# Sheet1.net
KiCad netlist of a schematic drawn in Altium Designer
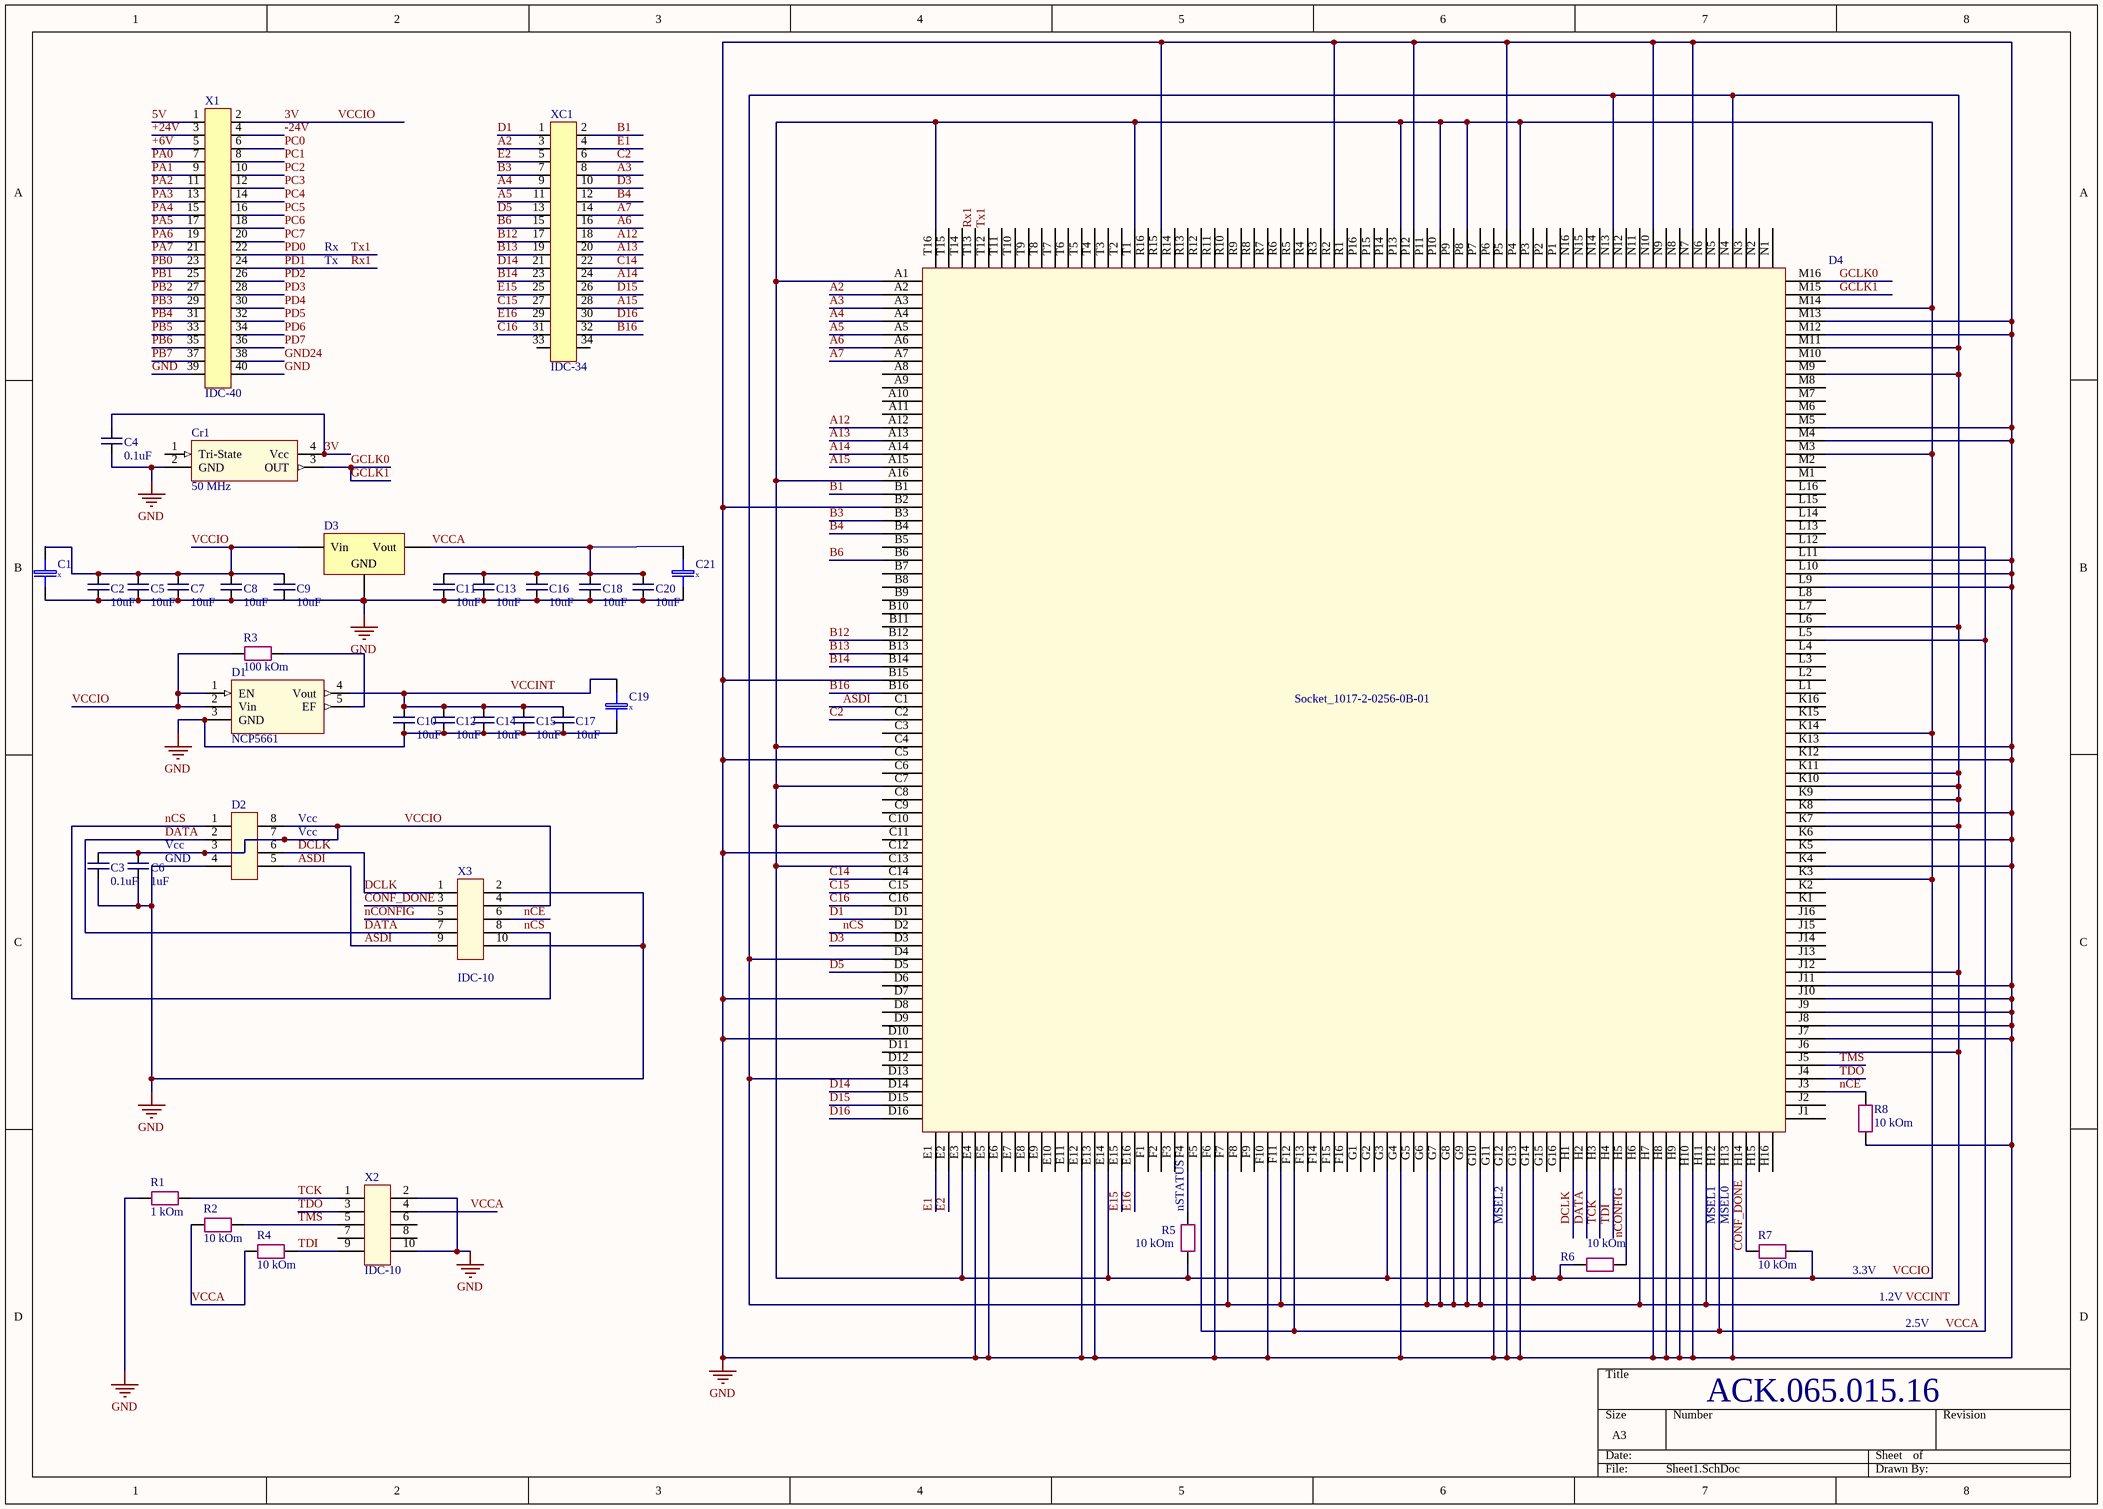
[diagram p0: Sheet1.SchDoc]

(export (version "E")
  (design (tool "Eeschema 10.0.6"))
  (components
    (comp (ref "C1")
      (value "x")
      (footprint "EL Case D (7343-31)")
      (description "EL Tantalum Case D (7343-31)")
      (libsource (lib "SMD-RCL") (part "EL Case D (7343-31)"))
    )
    (comp (ref "C2") (value "10uF") (footprint "RCU:C_0805") (libsource (lib "RCU") (part "capacitor 0805")))
    (comp (ref "C3") (value "0.1uF") (footprint "RCU:C_0805") (libsource (lib "RCU") (part "capacitor 0805")))
    (comp (ref "C4") (value "0.1uF") (footprint "RCU:C_0805") (libsource (lib "RCU") (part "capacitor 0805")))
    (comp (ref "C5") (value "10uF") (footprint "RCU:C_0805") (libsource (lib "RCU") (part "capacitor 0805")))
    (comp (ref "C6") (value "1uF") (footprint "RCU:C_0805") (libsource (lib "RCU") (part "capacitor 0805")))
    (comp (ref "C7") (value "10uF") (footprint "RCU:C_0805") (libsource (lib "RCU") (part "capacitor 0805")))
    (comp (ref "C8") (value "10uF") (footprint "RCU:C_0805") (libsource (lib "RCU") (part "capacitor 0805")))
    (comp (ref "C9") (value "10uF") (footprint "RCU:C_0805") (libsource (lib "RCU") (part "capacitor 0805")))
    (comp (ref "C10") (value "10uF") (footprint "RCU:C_0805") (libsource (lib "RCU") (part "capacitor 0805")))
    (comp (ref "C11") (value "10uF") (footprint "RCU:C_0805") (libsource (lib "RCU") (part "capacitor 0805")))
    (comp (ref "C12") (value "10uF") (footprint "RCU:C_0805") (libsource (lib "RCU") (part "capacitor 0805")))
    (comp (ref "C13") (value "10uF") (footprint "RCU:C_0805") (libsource (lib "RCU") (part "capacitor 0805")))
    (comp (ref "C14") (value "10uF") (footprint "RCU:C_0805") (libsource (lib "RCU") (part "capacitor 0805")))
    (comp (ref "C15") (value "10uF") (footprint "RCU:C_0805") (libsource (lib "RCU") (part "capacitor 0805")))
    (comp (ref "C16") (value "10uF") (footprint "RCU:C_0805") (libsource (lib "RCU") (part "capacitor 0805")))
    (comp (ref "C17") (value "10uF") (footprint "RCU:C_0805") (libsource (lib "RCU") (part "capacitor 0805")))
    (comp (ref "C18") (value "10uF") (footprint "RCU:C_0805") (libsource (lib "RCU") (part "capacitor 0805")))
    (comp (ref "C19")
      (value "x")
      (footprint "EL Case D (7343-31)")
      (description "EL Tantalum Case D (7343-31)")
      (libsource (lib "SMD-RCL") (part "EL Case D (7343-31)"))
    )
    (comp (ref "C20") (value "10uF") (footprint "RCU:C_0805") (libsource (lib "RCU") (part "capacitor 0805")))
    (comp (ref "C21")
      (value "x")
      (footprint "EL Case D (7343-31)")
      (description "EL Tantalum Case D (7343-31)")
      (libsource (lib "SMD-RCL") (part "EL Case D (7343-31)"))
    )
    (comp (ref "Cr1")
      (value "50 MHz")
      (footprint "quartz gen smd 5032")
      (libsource (lib "RCU") (part "quartz gen 5032"))
    )
    (comp (ref "D1") (value "NCP5661") (footprint "TO114P990-5_6M") (libsource (lib "RCU") (part "NCP5661")))
    (comp (ref "D2") (value "SOIC-8") (footprint "SOIC-8") (libsource (lib "RCU") (part "SOIC-8")))
    (comp (ref "D3")
      (value "LM1117-3.3")
      (footprint "TO252AA")
      (description "Voltage Regulator")
      (fields (field (name "PUBLISHER") "Altium Limited"))
      (libsource (lib "Miscellaneous Devices") (part "Volt Reg"))
    )
    (comp (ref "D4")
      (value "Socket_1017-2-0256-0B-01")
      (footprint "FBGA256")
      (libsource (lib "RCU") (part "Socket_1017-2-0256-0B-01"))
    )
    (comp (ref "R1") (value "1 kOm") (footprint "RCU:R_0805") (libsource (lib "RCU") (part "resistor 0805")))
    (comp (ref "R2") (value "10 kOm") (footprint "RCU:R_0805") (libsource (lib "RCU") (part "resistor 0805")))
    (comp (ref "R3")
      (value "100 kOm")
      (footprint "RCU:R_0805")
      (libsource (lib "RCU") (part "resistor 0805"))
    )
    (comp (ref "R4") (value "10 kOm") (footprint "RCU:R_0805") (libsource (lib "RCU") (part "resistor 0805")))
    (comp (ref "R5") (value "10 kOm") (footprint "RCU:R_0805") (libsource (lib "RCU") (part "resistor 0805")))
    (comp (ref "R6") (value "10 kOm") (footprint "RCU:R_0805") (libsource (lib "RCU") (part "resistor 0805")))
    (comp (ref "R7") (value "10 kOm") (footprint "RCU:R_0805") (libsource (lib "RCU") (part "resistor 0805")))
    (comp (ref "R8") (value "10 kOm") (footprint "RCU:R_0805") (libsource (lib "RCU") (part "resistor 0805")))
    (comp (ref "X1")
      (value "IDC-40")
      (footprint "IDC-40")
      (description "разъем 2529")
      (libsource (lib "RCU") (part "IDC-40"))
    )
    (comp (ref "X2")
      (value "IDC-10")
      (footprint "IDC-10")
      (description "разъем 4130")
      (libsource (lib "RCU") (part "IDC-10"))
    )
    (comp (ref "X3")
      (value "IDC-10")
      (footprint "IDC-10")
      (description "разъем 4130")
      (libsource (lib "RCU") (part "IDC-10"))
    )
    (comp (ref "XC1")
      (value "IDC-34")
      (footprint "IDC-34")
      (description "разъем 6556")
      (libsource (lib "RCU") (part "IDC-34"))
    )
  )
  (nets
    (net (code "1") (name "/+6V") (class "Default")
      (node (ref "X1") (pin "5") (pinfunction "5_5") (pintype "passive"))
    )
    (net (code "2") (name "/+24V") (class "Default")
      (node (ref "X1") (pin "3") (pinfunction "3_3") (pintype "passive"))
    )
    (net (code "3") (name "/-24V") (class "Default")
      (node (ref "X1") (pin "4") (pinfunction "4_4") (pintype "passive"))
    )
    (net (code "4") (name "/3V") (class "Default")
      (node (ref "C1") (pin "1") (pinfunction "+_1") (pintype "passive"))
      (node (ref "C2") (pin "2") (pinfunction "2_2") (pintype "passive"))
      (node (ref "C3") (pin "2") (pinfunction "2_2") (pintype "passive"))
      (node (ref "C4") (pin "2") (pinfunction "2_2") (pintype "passive"))
      (node (ref "C5") (pin "2") (pinfunction "2_2") (pintype "passive"))
      (node (ref "C6") (pin "2") (pinfunction "2_2") (pintype "passive"))
      (node (ref "C7") (pin "2") (pinfunction "2_2") (pintype "passive"))
      (node (ref "C8") (pin "2") (pinfunction "2_2") (pintype "passive"))
      (node (ref "C9") (pin "2") (pinfunction "2_2") (pintype "passive"))
      (node (ref "Cr1") (pin "4") (pinfunction "Vcc_4") (pintype "power_in"))
      (node (ref "D1") (pin "1") (pinfunction "EN_1") (pintype "input"))
      (node (ref "D1") (pin "2") (pinfunction "Vin_2") (pintype "power_in"))
      (node (ref "D2") (pin "3") (pinfunction "3_3") (pintype "passive"))
      (node (ref "D2") (pin "7") (pinfunction "7_7") (pintype "passive"))
      (node (ref "D2") (pin "8") (pinfunction "8_8") (pintype "passive"))
      (node (ref "D3") (pin "1") (pinfunction "Vin_1") (pintype "passive"))
      (node (ref "D4") (pin "A1") (pinfunction "A1_A1") (pintype "passive"))
      (node (ref "D4") (pin "A16") (pinfunction "A16_A16") (pintype "passive"))
      (node (ref "D4") (pin "C10") (pinfunction "C10_C10") (pintype "passive"))
      (node (ref "D4") (pin "C13") (pinfunction "C13_C13") (pintype "passive"))
      (node (ref "D4") (pin "C4") (pinfunction "C4_C4") (pintype "passive"))
      (node (ref "D4") (pin "C7") (pinfunction "C7_C7") (pintype "passive"))
      (node (ref "D4") (pin "E14") (pinfunction "E14_E14") (pintype "passive"))
      (node (ref "D4") (pin "E3") (pinfunction "E3_E3") (pintype "passive"))
      (node (ref "D4") (pin "G14") (pinfunction "G14_G14") (pintype "passive"))
      (node (ref "D4") (pin "G3") (pinfunction "G3_G3") (pintype "passive"))
      (node (ref "D4") (pin "K14") (pinfunction "K14_K14") (pintype "passive"))
      (node (ref "D4") (pin "K3") (pinfunction "K3_K3") (pintype "passive"))
      (node (ref "D4") (pin "M14") (pinfunction "M14_M14") (pintype "passive"))
      (node (ref "D4") (pin "M3") (pinfunction "M3_M3") (pintype "passive"))
      (node (ref "D4") (pin "P10") (pinfunction "P10_P10") (pintype "passive"))
      (node (ref "D4") (pin "P13") (pinfunction "P13_P13") (pintype "passive"))
      (node (ref "D4") (pin "P4") (pinfunction "P4_P4") (pintype "passive"))
      (node (ref "D4") (pin "P8") (pinfunction "P8_P8") (pintype "passive"))
      (node (ref "D4") (pin "T1") (pinfunction "T1_T1") (pintype "passive"))
      (node (ref "D4") (pin "T16") (pinfunction "T16_T16") (pintype "passive"))
      (node (ref "R3") (pin "1") (pinfunction "1_1") (pintype "passive"))
      (node (ref "R5") (pin "2") (pinfunction "2_2") (pintype "passive"))
      (node (ref "R6") (pin "1") (pinfunction "1_1") (pintype "passive"))
      (node (ref "R7") (pin "2") (pinfunction "2_2") (pintype "passive"))
      (node (ref "X1") (pin "2") (pinfunction "2_2") (pintype "passive"))
      (node (ref "X3") (pin "4") (pinfunction "4_4") (pintype "passive"))
    )
    (net (code "5") (name "/5V") (class "Default")
      (node (ref "X1") (pin "1") (pinfunction "0_1") (pintype "passive"))
    )
    (net (code "6") (name "/A2") (class "Default")
      (node (ref "D4") (pin "A2") (pinfunction "A2_A2") (pintype "passive"))
      (node (ref "XC1") (pin "3") (pinfunction "3_3") (pintype "passive"))
    )
    (net (code "7") (name "/A3") (class "Default")
      (node (ref "D4") (pin "A3") (pinfunction "A3_A3") (pintype "passive"))
      (node (ref "XC1") (pin "8") (pinfunction "8_8") (pintype "passive"))
    )
    (net (code "8") (name "/A4") (class "Default")
      (node (ref "D4") (pin "A4") (pinfunction "A4_A4") (pintype "passive"))
      (node (ref "XC1") (pin "9") (pinfunction "9_9") (pintype "passive"))
    )
    (net (code "9") (name "/A5") (class "Default")
      (node (ref "D4") (pin "A5") (pinfunction "A5_A5") (pintype "passive"))
      (node (ref "XC1") (pin "11") (pinfunction "11_11") (pintype "passive"))
    )
    (net (code "10") (name "/A6") (class "Default")
      (node (ref "D4") (pin "A6") (pinfunction "A6_A6") (pintype "passive"))
      (node (ref "XC1") (pin "16") (pinfunction "16_16") (pintype "passive"))
    )
    (net (code "11") (name "/A7") (class "Default")
      (node (ref "D4") (pin "A7") (pinfunction "A7_A7") (pintype "passive"))
      (node (ref "XC1") (pin "14") (pinfunction "14_14") (pintype "passive"))
    )
    (net (code "12") (name "/A12") (class "Default")
      (node (ref "D4") (pin "A12") (pinfunction "A12_A12") (pintype "passive"))
      (node (ref "XC1") (pin "18") (pinfunction "18_18") (pintype "passive"))
    )
    (net (code "13") (name "/A13") (class "Default")
      (node (ref "D4") (pin "A13") (pinfunction "A13_A13") (pintype "passive"))
      (node (ref "XC1") (pin "20") (pinfunction "20_20") (pintype "passive"))
    )
    (net (code "14") (name "/A14") (class "Default")
      (node (ref "D4") (pin "A14") (pinfunction "A14_A14") (pintype "passive"))
      (node (ref "XC1") (pin "24") (pinfunction "24_24") (pintype "passive"))
    )
    (net (code "15") (name "/A15") (class "Default")
      (node (ref "D4") (pin "A15") (pinfunction "A15_A15") (pintype "passive"))
      (node (ref "XC1") (pin "28") (pinfunction "28_28") (pintype "passive"))
    )
    (net (code "16") (name "/ASDI") (class "Default")
      (node (ref "D2") (pin "5") (pinfunction "5_5") (pintype "passive"))
      (node (ref "D4") (pin "C1") (pinfunction "C1_C1") (pintype "passive"))
      (node (ref "X3") (pin "9") (pinfunction "9_9") (pintype "passive"))
    )
    (net (code "17") (name "/B1") (class "Default")
      (node (ref "D4") (pin "B1") (pinfunction "B1_B1") (pintype "passive"))
      (node (ref "XC1") (pin "2") (pinfunction "2_2") (pintype "passive"))
    )
    (net (code "18") (name "/B3") (class "Default")
      (node (ref "D4") (pin "B3") (pinfunction "B3_B3") (pintype "passive"))
      (node (ref "XC1") (pin "7") (pinfunction "7_7") (pintype "passive"))
    )
    (net (code "19") (name "/B4") (class "Default")
      (node (ref "D4") (pin "B4") (pinfunction "B4_B4") (pintype "passive"))
      (node (ref "XC1") (pin "12") (pinfunction "12_12") (pintype "passive"))
    )
    (net (code "20") (name "/B6") (class "Default")
      (node (ref "D4") (pin "B6") (pinfunction "B6_B6") (pintype "passive"))
      (node (ref "XC1") (pin "15") (pinfunction "15_15") (pintype "passive"))
    )
    (net (code "21") (name "/B12") (class "Default")
      (node (ref "D4") (pin "B12") (pinfunction "B12_B12") (pintype "passive"))
      (node (ref "XC1") (pin "17") (pinfunction "17_17") (pintype "passive"))
    )
    (net (code "22") (name "/B13") (class "Default")
      (node (ref "D4") (pin "B13") (pinfunction "B13_B13") (pintype "passive"))
      (node (ref "XC1") (pin "19") (pinfunction "19_19") (pintype "passive"))
    )
    (net (code "23") (name "/B14") (class "Default")
      (node (ref "D4") (pin "B14") (pinfunction "B14_B14") (pintype "passive"))
      (node (ref "XC1") (pin "23") (pinfunction "23_23") (pintype "passive"))
    )
    (net (code "24") (name "/B16") (class "Default")
      (node (ref "D4") (pin "B16") (pinfunction "B16_B16") (pintype "passive"))
      (node (ref "XC1") (pin "32") (pinfunction "32_32") (pintype "passive"))
    )
    (net (code "25") (name "/C2") (class "Default")
      (node (ref "D4") (pin "C2") (pinfunction "C2_C2") (pintype "passive"))
      (node (ref "XC1") (pin "6") (pinfunction "6_6") (pintype "passive"))
    )
    (net (code "26") (name "/C14") (class "Default")
      (node (ref "D4") (pin "C14") (pinfunction "C14_C14") (pintype "passive"))
      (node (ref "XC1") (pin "22") (pinfunction "22_22") (pintype "passive"))
    )
    (net (code "27") (name "/C15") (class "Default")
      (node (ref "D4") (pin "C15") (pinfunction "C15_C15") (pintype "passive"))
      (node (ref "XC1") (pin "27") (pinfunction "27_27") (pintype "passive"))
    )
    (net (code "28") (name "/C16") (class "Default")
      (node (ref "D4") (pin "C16") (pinfunction "C16_C16") (pintype "passive"))
      (node (ref "XC1") (pin "31") (pinfunction "31_31") (pintype "passive"))
    )
    (net (code "29") (name "/CONF_DONE") (class "Default")
      (node (ref "D4") (pin "H14") (pinfunction "H14_H14") (pintype "passive"))
      (node (ref "R7") (pin "1") (pinfunction "1_1") (pintype "passive"))
      (node (ref "X3") (pin "3") (pinfunction "3_3") (pintype "passive"))
    )
    (net (code "30") (name "/D1") (class "Default")
      (node (ref "D4") (pin "D1") (pinfunction "D1_D1") (pintype "passive"))
      (node (ref "XC1") (pin "1") (pinfunction "0_1") (pintype "passive"))
    )
    (net (code "31") (name "/D3") (class "Default")
      (node (ref "D4") (pin "D3") (pinfunction "D3_D3") (pintype "passive"))
      (node (ref "XC1") (pin "10") (pinfunction "10_10") (pintype "passive"))
    )
    (net (code "32") (name "/D5") (class "Default")
      (node (ref "D4") (pin "D5") (pinfunction "D5_D5") (pintype "passive"))
      (node (ref "XC1") (pin "13") (pinfunction "13_13") (pintype "passive"))
    )
    (net (code "33") (name "/D14") (class "Default")
      (node (ref "D4") (pin "D14") (pinfunction "D14_D14") (pintype "passive"))
      (node (ref "XC1") (pin "21") (pinfunction "21_21") (pintype "passive"))
    )
    (net (code "34") (name "/D15") (class "Default")
      (node (ref "D4") (pin "D15") (pinfunction "D15_D15") (pintype "passive"))
      (node (ref "XC1") (pin "26") (pinfunction "26_26") (pintype "passive"))
    )
    (net (code "35") (name "/D16") (class "Default")
      (node (ref "D4") (pin "D16") (pinfunction "D16_D16") (pintype "passive"))
      (node (ref "XC1") (pin "30") (pinfunction "30_30") (pintype "passive"))
    )
    (net (code "36") (name "/DATA") (class "Default")
      (node (ref "D2") (pin "2") (pinfunction "2_2") (pintype "passive"))
      (node (ref "D4") (pin "H2") (pinfunction "H2_H2") (pintype "passive"))
      (node (ref "X3") (pin "7") (pinfunction "7_7") (pintype "passive"))
    )
    (net (code "37") (name "/DCLK") (class "Default")
      (node (ref "D2") (pin "6") (pinfunction "6_6") (pintype "passive"))
      (node (ref "D4") (pin "H1") (pinfunction "H1_H1") (pintype "passive"))
      (node (ref "X3") (pin "1") (pinfunction "1_1") (pintype "passive"))
    )
    (net (code "38") (name "/E1") (class "Default")
      (node (ref "D4") (pin "E1") (pinfunction "E1_E1") (pintype "passive"))
      (node (ref "XC1") (pin "4") (pinfunction "4_4") (pintype "passive"))
    )
    (net (code "39") (name "/E2") (class "Default")
      (node (ref "D4") (pin "E2") (pinfunction "E2_E2") (pintype "passive"))
      (node (ref "XC1") (pin "5") (pinfunction "5_5") (pintype "passive"))
    )
    (net (code "40") (name "/E15") (class "Default")
      (node (ref "D4") (pin "E15") (pinfunction "E15_E15") (pintype "passive"))
      (node (ref "XC1") (pin "25") (pinfunction "25_25") (pintype "passive"))
    )
    (net (code "41") (name "/E16") (class "Default")
      (node (ref "D4") (pin "E16") (pinfunction "E16_E16") (pintype "passive"))
      (node (ref "XC1") (pin "29") (pinfunction "29_29") (pintype "passive"))
    )
    (net (code "42") (name "/GCLK0") (class "Default")
      (node (ref "Cr1") (pin "3") (pinfunction "OUT_3") (pintype "output"))
      (node (ref "D4") (pin "M15") (pinfunction "M15_M15") (pintype "passive"))
      (node (ref "D4") (pin "M16") (pinfunction "M16_M16") (pintype "passive"))
    )
    (net (code "43") (name "/GND24") (class "Default")
      (node (ref "X1") (pin "38") (pinfunction "38_38") (pintype "passive"))
    )
    (net (code "44") (name "/PA0") (class "Default")
      (node (ref "X1") (pin "7") (pinfunction "7_7") (pintype "passive"))
    )
    (net (code "45") (name "/PA1") (class "Default")
      (node (ref "X1") (pin "9") (pinfunction "9_9") (pintype "passive"))
    )
    (net (code "46") (name "/PA2") (class "Default")
      (node (ref "X1") (pin "11") (pinfunction "11_11") (pintype "passive"))
    )
    (net (code "47") (name "/PA3") (class "Default")
      (node (ref "X1") (pin "13") (pinfunction "13_13") (pintype "passive"))
    )
    (net (code "48") (name "/PA4") (class "Default")
      (node (ref "X1") (pin "15") (pinfunction "15_15") (pintype "passive"))
    )
    (net (code "49") (name "/PA5") (class "Default")
      (node (ref "X1") (pin "17") (pinfunction "17_17") (pintype "passive"))
    )
    (net (code "50") (name "/PA6") (class "Default")
      (node (ref "X1") (pin "19") (pinfunction "19_19") (pintype "passive"))
    )
    (net (code "51") (name "/PA7") (class "Default")
      (node (ref "X1") (pin "21") (pinfunction "21_21") (pintype "passive"))
    )
    (net (code "52") (name "/PB0") (class "Default")
      (node (ref "X1") (pin "23") (pinfunction "23_23") (pintype "passive"))
    )
    (net (code "53") (name "/PB1") (class "Default")
      (node (ref "X1") (pin "25") (pinfunction "25_25") (pintype "passive"))
    )
    (net (code "54") (name "/PB2") (class "Default")
      (node (ref "X1") (pin "27") (pinfunction "27_27") (pintype "passive"))
    )
    (net (code "55") (name "/PB3") (class "Default")
      (node (ref "X1") (pin "29") (pinfunction "29_29") (pintype "passive"))
    )
    (net (code "56") (name "/PB4") (class "Default")
      (node (ref "X1") (pin "31") (pinfunction "31_31") (pintype "passive"))
    )
    (net (code "57") (name "/PB5") (class "Default")
      (node (ref "X1") (pin "33") (pinfunction "33_33") (pintype "passive"))
    )
    (net (code "58") (name "/PB6") (class "Default")
      (node (ref "X1") (pin "35") (pinfunction "35_35") (pintype "passive"))
    )
    (net (code "59") (name "/PB7") (class "Default")
      (node (ref "X1") (pin "37") (pinfunction "37_37") (pintype "passive"))
    )
    (net (code "60") (name "/PC0") (class "Default")
      (node (ref "X1") (pin "6") (pinfunction "6_6") (pintype "passive"))
    )
    (net (code "61") (name "/PC1") (class "Default")
      (node (ref "X1") (pin "8") (pinfunction "8_8") (pintype "passive"))
    )
    (net (code "62") (name "/PC2") (class "Default")
      (node (ref "X1") (pin "10") (pinfunction "10_10") (pintype "passive"))
    )
    (net (code "63") (name "/PC3") (class "Default")
      (node (ref "X1") (pin "12") (pinfunction "12_12") (pintype "passive"))
    )
    (net (code "64") (name "/PC4") (class "Default")
      (node (ref "X1") (pin "14") (pinfunction "14_14") (pintype "passive"))
    )
    (net (code "65") (name "/PC5") (class "Default")
      (node (ref "X1") (pin "16") (pinfunction "16_16") (pintype "passive"))
    )
    (net (code "66") (name "/PC6") (class "Default")
      (node (ref "X1") (pin "18") (pinfunction "18_18") (pintype "passive"))
    )
    (net (code "67") (name "/PC7") (class "Default")
      (node (ref "X1") (pin "20") (pinfunction "20_20") (pintype "passive"))
    )
    (net (code "68") (name "/PD0") (class "Default")
      (node (ref "D4") (pin "T12") (pinfunction "T12_T12") (pintype "passive"))
      (node (ref "X1") (pin "22") (pinfunction "22_22") (pintype "passive"))
    )
    (net (code "69") (name "/PD1") (class "Default")
      (node (ref "D4") (pin "T13") (pinfunction "T13_T13") (pintype "passive"))
      (node (ref "X1") (pin "24") (pinfunction "24_24") (pintype "passive"))
    )
    (net (code "70") (name "/PD2") (class "Default")
      (node (ref "X1") (pin "26") (pinfunction "26_26") (pintype "passive"))
    )
    (net (code "71") (name "/PD3") (class "Default")
      (node (ref "X1") (pin "28") (pinfunction "28_28") (pintype "passive"))
    )
    (net (code "72") (name "/PD4") (class "Default")
      (node (ref "X1") (pin "30") (pinfunction "30_30") (pintype "passive"))
    )
    (net (code "73") (name "/PD5") (class "Default")
      (node (ref "X1") (pin "32") (pinfunction "32_32") (pintype "passive"))
    )
    (net (code "74") (name "/PD6") (class "Default")
      (node (ref "X1") (pin "34") (pinfunction "34_34") (pintype "passive"))
    )
    (net (code "75") (name "/PD7") (class "Default")
      (node (ref "X1") (pin "36") (pinfunction "36_36") (pintype "passive"))
    )
    (net (code "76") (name "/TCK") (class "Default")
      (node (ref "D4") (pin "H3") (pinfunction "H3_H3") (pintype "passive"))
      (node (ref "R1") (pin "2") (pinfunction "2_2") (pintype "passive"))
      (node (ref "X2") (pin "1") (pinfunction "1_1") (pintype "passive"))
    )
    (net (code "77") (name "/TDI") (class "Default")
      (node (ref "D4") (pin "H4") (pinfunction "H4_H4") (pintype "passive"))
      (node (ref "R4") (pin "2") (pinfunction "2_2") (pintype "passive"))
      (node (ref "X2") (pin "9") (pinfunction "9_9") (pintype "passive"))
    )
    (net (code "78") (name "/TDO") (class "Default")
      (node (ref "D4") (pin "J4") (pinfunction "J4_J4") (pintype "passive"))
      (node (ref "X2") (pin "3") (pinfunction "3_3") (pintype "passive"))
    )
    (net (code "79") (name "/TMS") (class "Default")
      (node (ref "D4") (pin "J5") (pinfunction "J5_J5") (pintype "passive"))
      (node (ref "R2") (pin "2") (pinfunction "2_2") (pintype "passive"))
      (node (ref "X2") (pin "5") (pinfunction "5_5") (pintype "passive"))
    )
    (net (code "80") (name "/VCCA") (class "Default")
      (node (ref "C11") (pin "2") (pinfunction "2_2") (pintype "passive"))
      (node (ref "C13") (pin "2") (pinfunction "2_2") (pintype "passive"))
      (node (ref "C16") (pin "2") (pinfunction "2_2") (pintype "passive"))
      (node (ref "C18") (pin "2") (pinfunction "2_2") (pintype "passive"))
      (node (ref "C20") (pin "2") (pinfunction "2_2") (pintype "passive"))
      (node (ref "C21") (pin "1") (pinfunction "+_1") (pintype "passive"))
      (node (ref "D3") (pin "3") (pinfunction "Vout_3") (pintype "passive"))
      (node (ref "D4") (pin "F12") (pinfunction "F12_F12") (pintype "passive"))
      (node (ref "D4") (pin "F5") (pinfunction "F5_F5") (pintype "passive"))
      (node (ref "D4") (pin "H12") (pinfunction "H12_H12") (pintype "passive"))
      (node (ref "D4") (pin "L12") (pinfunction "L12_L12") (pintype "passive"))
      (node (ref "D4") (pin "L5") (pinfunction "L5_L5") (pintype "passive"))
      (node (ref "R2") (pin "1") (pinfunction "1_1") (pintype "passive"))
      (node (ref "R4") (pin "1") (pinfunction "1_1") (pintype "passive"))
      (node (ref "X2") (pin "4") (pinfunction "4_4") (pintype "passive"))
    )
    (net (code "81") (name "/VCCINT") (class "Default")
      (node (ref "C10") (pin "2") (pinfunction "2_2") (pintype "passive"))
      (node (ref "C12") (pin "2") (pinfunction "2_2") (pintype "passive"))
      (node (ref "C14") (pin "2") (pinfunction "2_2") (pintype "passive"))
      (node (ref "C15") (pin "2") (pinfunction "2_2") (pintype "passive"))
      (node (ref "C17") (pin "2") (pinfunction "2_2") (pintype "passive"))
      (node (ref "C19") (pin "1") (pinfunction "+_1") (pintype "passive"))
      (node (ref "D1") (pin "4") (pinfunction "Vout_4") (pintype "output"))
      (node (ref "D4") (pin "D13") (pinfunction "D13_D13") (pintype "passive"))
      (node (ref "D4") (pin "D4") (pinfunction "D4_D4") (pintype "passive"))
      (node (ref "D4") (pin "F11") (pinfunction "F11_F11") (pintype "passive"))
      (node (ref "D4") (pin "F7") (pinfunction "F7_F7") (pintype "passive"))
      (node (ref "D4") (pin "G10") (pinfunction "G10_G10") (pintype "passive"))
      (node (ref "D4") (pin "G6") (pinfunction "G6_G6") (pintype "passive"))
      (node (ref "D4") (pin "G7") (pinfunction "G7_G7") (pintype "passive"))
      (node (ref "D4") (pin "G8") (pinfunction "G8_G8") (pintype "passive"))
      (node (ref "D4") (pin "G9") (pinfunction "G9_G9") (pintype "passive"))
      (node (ref "D4") (pin "H11") (pinfunction "H11_H11") (pintype "passive"))
      (node (ref "D4") (pin "H6") (pinfunction "H6_H6") (pintype "passive"))
      (node (ref "D4") (pin "J12") (pinfunction "J12_J12") (pintype "passive"))
      (node (ref "D4") (pin "J6") (pinfunction "J6_J6") (pintype "passive"))
      (node (ref "D4") (pin "K10") (pinfunction "K10_K10") (pintype "passive"))
      (node (ref "D4") (pin "K11") (pinfunction "K11_K11") (pintype "passive"))
      (node (ref "D4") (pin "K7") (pinfunction "K7_K7") (pintype "passive"))
      (node (ref "D4") (pin "K9") (pinfunction "K9_K9") (pintype "passive"))
      (node (ref "D4") (pin "L6") (pinfunction "L6_L6") (pintype "passive"))
      (node (ref "D4") (pin "M11") (pinfunction "M11_M11") (pintype "passive"))
      (node (ref "D4") (pin "M9") (pinfunction "M9_M9") (pintype "passive"))
      (node (ref "D4") (pin "N13") (pinfunction "N13_N13") (pintype "passive"))
      (node (ref "D4") (pin "N4") (pinfunction "N4_N4") (pintype "passive"))
    )
    (net (code "82") (name "/nCE") (class "Default")
      (node (ref "D4") (pin "J3") (pinfunction "J3_J3") (pintype "passive"))
      (node (ref "R8") (pin "2") (pinfunction "2_2") (pintype "passive"))
      (node (ref "X3") (pin "6") (pinfunction "6_6") (pintype "passive"))
    )
    (net (code "83") (name "/nCONFIG") (class "Default")
      (node (ref "D4") (pin "H5") (pinfunction "H5_H5") (pintype "passive"))
      (node (ref "R6") (pin "2") (pinfunction "2_2") (pintype "passive"))
      (node (ref "X3") (pin "5") (pinfunction "5_5") (pintype "passive"))
    )
    (net (code "84") (name "/nCS") (class "Default")
      (node (ref "D2") (pin "1") (pinfunction "1_1") (pintype "passive"))
      (node (ref "D4") (pin "D2") (pinfunction "D2_D2") (pintype "passive"))
      (node (ref "X3") (pin "8") (pinfunction "8_8") (pintype "passive"))
    )
    (net (code "85") (name "GND") (class "Default")
      (node (ref "C1") (pin "2") (pinfunction "-_2") (pintype "passive"))
      (node (ref "C10") (pin "1") (pinfunction "1_1") (pintype "passive"))
      (node (ref "C11") (pin "1") (pinfunction "1_1") (pintype "passive"))
      (node (ref "C12") (pin "1") (pinfunction "1_1") (pintype "passive"))
      (node (ref "C13") (pin "1") (pinfunction "1_1") (pintype "passive"))
      (node (ref "C14") (pin "1") (pinfunction "1_1") (pintype "passive"))
      (node (ref "C15") (pin "1") (pinfunction "1_1") (pintype "passive"))
      (node (ref "C16") (pin "1") (pinfunction "1_1") (pintype "passive"))
      (node (ref "C17") (pin "1") (pinfunction "1_1") (pintype "passive"))
      (node (ref "C18") (pin "1") (pinfunction "1_1") (pintype "passive"))
      (node (ref "C19") (pin "2") (pinfunction "-_2") (pintype "passive"))
      (node (ref "C2") (pin "1") (pinfunction "1_1") (pintype "passive"))
      (node (ref "C20") (pin "1") (pinfunction "1_1") (pintype "passive"))
      (node (ref "C21") (pin "2") (pinfunction "-_2") (pintype "passive"))
      (node (ref "C3") (pin "1") (pinfunction "1_1") (pintype "passive"))
      (node (ref "C4") (pin "1") (pinfunction "1_1") (pintype "passive"))
      (node (ref "C5") (pin "1") (pinfunction "1_1") (pintype "passive"))
      (node (ref "C6") (pin "1") (pinfunction "1_1") (pintype "passive"))
      (node (ref "C7") (pin "1") (pinfunction "1_1") (pintype "passive"))
      (node (ref "C8") (pin "1") (pinfunction "1_1") (pintype "passive"))
      (node (ref "C9") (pin "1") (pinfunction "1_1") (pintype "passive"))
      (node (ref "Cr1") (pin "2") (pinfunction "GND_2") (pintype "power_in"))
      (node (ref "D1") (pin "3") (pinfunction "GND_3") (pintype "power_in"))
      (node (ref "D2") (pin "4") (pinfunction "4_4") (pintype "passive"))
      (node (ref "D3") (pin "2") (pinfunction "GND_2") (pintype "passive"))
      (node (ref "D4") (pin "B15") (pinfunction "B15_B15") (pintype "passive"))
      (node (ref "D4") (pin "B2") (pinfunction "B2_B2") (pintype "passive"))
      (node (ref "D4") (pin "C12") (pinfunction "C12_C12") (pintype "passive"))
      (node (ref "D4") (pin "C5") (pinfunction "C5_C5") (pintype "passive"))
      (node (ref "D4") (pin "D10") (pinfunction "D10_D10") (pintype "passive"))
      (node (ref "D4") (pin "D7") (pinfunction "D7_D7") (pintype "passive"))
      (node (ref "D4") (pin "E12") (pinfunction "E12_E12") (pintype "passive"))
      (node (ref "D4") (pin "E13") (pinfunction "E13_E13") (pintype "passive"))
      (node (ref "D4") (pin "E4") (pinfunction "E4_E4") (pintype "passive"))
      (node (ref "D4") (pin "E5") (pinfunction "E5_E5") (pintype "passive"))
      (node (ref "D4") (pin "F10") (pinfunction "F10_F10") (pintype "passive"))
      (node (ref "D4") (pin "F6") (pinfunction "F6_F6") (pintype "passive"))
      (node (ref "D4") (pin "G11") (pinfunction "G11_G11") (pintype "passive"))
      (node (ref "D4") (pin "G12") (pinfunction "G12_G12") (pintype "passive"))
      (node (ref "D4") (pin "G13") (pinfunction "G13_G13") (pintype "passive"))
      (node (ref "D4") (pin "G4") (pinfunction "G4_G4") (pintype "passive"))
      (node (ref "D4") (pin "H10") (pinfunction "H10_H10") (pintype "passive"))
      (node (ref "D4") (pin "H13") (pinfunction "H13_H13") (pintype "passive"))
      (node (ref "D4") (pin "H7") (pinfunction "H7_H7") (pintype "passive"))
      (node (ref "D4") (pin "H8") (pinfunction "H8_H8") (pintype "passive"))
      (node (ref "D4") (pin "H9") (pinfunction "H9_H9") (pintype "passive"))
      (node (ref "D4") (pin "J10") (pinfunction "J10_J10") (pintype "passive"))
      (node (ref "D4") (pin "J11") (pinfunction "J11_J11") (pintype "passive"))
      (node (ref "D4") (pin "J7") (pinfunction "J7_J7") (pintype "passive"))
      (node (ref "D4") (pin "J8") (pinfunction "J8_J8") (pintype "passive"))
      (node (ref "D4") (pin "J9") (pinfunction "J9_J9") (pintype "passive"))
      (node (ref "D4") (pin "K12") (pinfunction "K12_K12") (pintype "passive"))
      (node (ref "D4") (pin "K13") (pinfunction "K13_K13") (pintype "passive"))
      (node (ref "D4") (pin "K4") (pinfunction "K4_K4") (pintype "passive"))
      (node (ref "D4") (pin "K6") (pinfunction "K6_K6") (pintype "passive"))
      (node (ref "D4") (pin "K8") (pinfunction "K8_K8") (pintype "passive"))
      (node (ref "D4") (pin "L10") (pinfunction "L10_L10") (pintype "passive"))
      (node (ref "D4") (pin "L11") (pinfunction "L11_L11") (pintype "passive"))
      (node (ref "D4") (pin "L9") (pinfunction "L9_L9") (pintype "passive"))
      (node (ref "D4") (pin "M12") (pinfunction "M12_M12") (pintype "passive"))
      (node (ref "D4") (pin "M13") (pinfunction "M13_M13") (pintype "passive"))
      (node (ref "D4") (pin "M4") (pinfunction "M4_M4") (pintype "passive"))
      (node (ref "D4") (pin "M5") (pinfunction "M5_M5") (pintype "passive"))
      (node (ref "D4") (pin "N10") (pinfunction "N10_N10") (pintype "passive"))
      (node (ref "D4") (pin "N7") (pinfunction "N7_N7") (pintype "passive"))
      (node (ref "D4") (pin "P12") (pinfunction "P12_P12") (pintype "passive"))
      (node (ref "D4") (pin "P5") (pinfunction "P5_P5") (pintype "passive"))
      (node (ref "D4") (pin "R15") (pinfunction "R15_R15") (pintype "passive"))
      (node (ref "D4") (pin "R2") (pinfunction "R2_R2") (pintype "passive"))
      (node (ref "R1") (pin "1") (pinfunction "1_1") (pintype "passive"))
      (node (ref "R8") (pin "1") (pinfunction "1_1") (pintype "passive"))
      (node (ref "X1") (pin "39") (pinfunction "39_39") (pintype "passive"))
      (node (ref "X1") (pin "40") (pinfunction "40_40") (pintype "passive"))
      (node (ref "X2") (pin "10") (pinfunction "10_10") (pintype "passive"))
      (node (ref "X2") (pin "2") (pinfunction "2_2") (pintype "passive"))
      (node (ref "X3") (pin "10") (pinfunction "10_10") (pintype "passive"))
      (node (ref "X3") (pin "2") (pinfunction "2_2") (pintype "passive"))
    )
    (net (code "86") (name "Net-(D1-EF)") (class "Default")
      (node (ref "D1") (pin "5") (pinfunction "EF_5") (pintype "output"))
      (node (ref "R3") (pin "2") (pinfunction "2_2") (pintype "passive"))
    )
    (net (code "87") (name "Net-(D4-PadF4)") (class "Default")
      (node (ref "D4") (pin "F4") (pinfunction "F4_F4") (pintype "passive"))
      (node (ref "R5") (pin "1") (pinfunction "1_1") (pintype "passive"))
    )
    (net (code "88") (name "unconnected-(Cr1-Tri-State-Pad1)") (class "Default")
      (node (ref "Cr1") (pin "1") (pinfunction "Tri-State_1") (pintype "input"))
    )
    (net (code "89") (name "unconnected-(D4-PadA8)") (class "Default")
      (node (ref "D4") (pin "A8") (pinfunction "A8_A8") (pintype "passive"))
    )
    (net (code "90") (name "unconnected-(D4-PadA9)") (class "Default")
      (node (ref "D4") (pin "A9") (pinfunction "A9_A9") (pintype "passive"))
    )
    (net (code "91") (name "unconnected-(D4-PadA10)") (class "Default")
      (node (ref "D4") (pin "A10") (pinfunction "A10_A10") (pintype "passive"))
    )
    (net (code "92") (name "unconnected-(D4-PadA11)") (class "Default")
      (node (ref "D4") (pin "A11") (pinfunction "A11_A11") (pintype "passive"))
    )
    (net (code "93") (name "unconnected-(D4-PadB5)") (class "Default")
      (node (ref "D4") (pin "B5") (pinfunction "B5_B5") (pintype "passive"))
    )
    (net (code "94") (name "unconnected-(D4-PadB7)") (class "Default")
      (node (ref "D4") (pin "B7") (pinfunction "B7_B7") (pintype "passive"))
    )
    (net (code "95") (name "unconnected-(D4-PadB8)") (class "Default")
      (node (ref "D4") (pin "B8") (pinfunction "B8_B8") (pintype "passive"))
    )
    (net (code "96") (name "unconnected-(D4-PadB9)") (class "Default")
      (node (ref "D4") (pin "B9") (pinfunction "B9_B9") (pintype "passive"))
    )
    (net (code "97") (name "unconnected-(D4-PadB10)") (class "Default")
      (node (ref "D4") (pin "B10") (pinfunction "B10_B10") (pintype "passive"))
    )
    (net (code "98") (name "unconnected-(D4-PadB11)") (class "Default")
      (node (ref "D4") (pin "B11") (pinfunction "B11_B11") (pintype "passive"))
    )
    (net (code "99") (name "unconnected-(D4-PadC3)") (class "Default")
      (node (ref "D4") (pin "C3") (pinfunction "C3_C3") (pintype "passive"))
    )
    (net (code "100") (name "unconnected-(D4-PadC6)") (class "Default")
      (node (ref "D4") (pin "C6") (pinfunction "C6_C6") (pintype "passive"))
    )
    (net (code "101") (name "unconnected-(D4-PadC8)") (class "Default")
      (node (ref "D4") (pin "C8") (pinfunction "C8_C8") (pintype "passive"))
    )
    (net (code "102") (name "unconnected-(D4-PadC9)") (class "Default")
      (node (ref "D4") (pin "C9") (pinfunction "C9_C9") (pintype "passive"))
    )
    (net (code "103") (name "unconnected-(D4-PadC11)") (class "Default")
      (node (ref "D4") (pin "C11") (pinfunction "C11_C11") (pintype "passive"))
    )
    (net (code "104") (name "unconnected-(D4-PadD6)") (class "Default")
      (node (ref "D4") (pin "D6") (pinfunction "D6_D6") (pintype "passive"))
    )
    (net (code "105") (name "unconnected-(D4-PadD8)") (class "Default")
      (node (ref "D4") (pin "D8") (pinfunction "D8_D8") (pintype "passive"))
    )
    (net (code "106") (name "unconnected-(D4-PadD9)") (class "Default")
      (node (ref "D4") (pin "D9") (pinfunction "D9_D9") (pintype "passive"))
    )
    (net (code "107") (name "unconnected-(D4-PadD11)") (class "Default")
      (node (ref "D4") (pin "D11") (pinfunction "D11_D11") (pintype "passive"))
    )
    (net (code "108") (name "unconnected-(D4-PadD12)") (class "Default")
      (node (ref "D4") (pin "D12") (pinfunction "D12_D12") (pintype "passive"))
    )
    (net (code "109") (name "unconnected-(D4-PadE6)") (class "Default")
      (node (ref "D4") (pin "E6") (pinfunction "E6_E6") (pintype "passive"))
    )
    (net (code "110") (name "unconnected-(D4-PadE7)") (class "Default")
      (node (ref "D4") (pin "E7") (pinfunction "E7_E7") (pintype "passive"))
    )
    (net (code "111") (name "unconnected-(D4-PadE8)") (class "Default")
      (node (ref "D4") (pin "E8") (pinfunction "E8_E8") (pintype "passive"))
    )
    (net (code "112") (name "unconnected-(D4-PadE9)") (class "Default")
      (node (ref "D4") (pin "E9") (pinfunction "E9_E9") (pintype "passive"))
    )
    (net (code "113") (name "unconnected-(D4-PadE10)") (class "Default")
      (node (ref "D4") (pin "E10") (pinfunction "E10_E10") (pintype "passive"))
    )
    (net (code "114") (name "unconnected-(D4-PadE11)") (class "Default")
      (node (ref "D4") (pin "E11") (pinfunction "E11_E11") (pintype "passive"))
    )
    (net (code "115") (name "unconnected-(D4-PadF1)") (class "Default")
      (node (ref "D4") (pin "F1") (pinfunction "F1_F1") (pintype "passive"))
    )
    (net (code "116") (name "unconnected-(D4-PadF2)") (class "Default")
      (node (ref "D4") (pin "F2") (pinfunction "F2_F2") (pintype "passive"))
    )
    (net (code "117") (name "unconnected-(D4-PadF3)") (class "Default")
      (node (ref "D4") (pin "F3") (pinfunction "F3_F3") (pintype "passive"))
    )
    (net (code "118") (name "unconnected-(D4-PadF8)") (class "Default")
      (node (ref "D4") (pin "F8") (pinfunction "F8_F8") (pintype "passive"))
    )
    (net (code "119") (name "unconnected-(D4-PadF9)") (class "Default")
      (node (ref "D4") (pin "F9") (pinfunction "F9_F9") (pintype "passive"))
    )
    (net (code "120") (name "unconnected-(D4-PadF13)") (class "Default")
      (node (ref "D4") (pin "F13") (pinfunction "F13_F13") (pintype "passive"))
    )
    (net (code "121") (name "unconnected-(D4-PadF14)") (class "Default")
      (node (ref "D4") (pin "F14") (pinfunction "F14_F14") (pintype "passive"))
    )
    (net (code "122") (name "unconnected-(D4-PadF15)") (class "Default")
      (node (ref "D4") (pin "F15") (pinfunction "F15_F15") (pintype "passive"))
    )
    (net (code "123") (name "unconnected-(D4-PadF16)") (class "Default")
      (node (ref "D4") (pin "F16") (pinfunction "F16_F16") (pintype "passive"))
    )
    (net (code "124") (name "unconnected-(D4-PadG1)") (class "Default")
      (node (ref "D4") (pin "G1") (pinfunction "G1_G1") (pintype "passive"))
    )
    (net (code "125") (name "unconnected-(D4-PadG2)") (class "Default")
      (node (ref "D4") (pin "G2") (pinfunction "G2_G2") (pintype "passive"))
    )
    (net (code "126") (name "unconnected-(D4-PadG5)") (class "Default")
      (node (ref "D4") (pin "G5") (pinfunction "G5_G5") (pintype "passive"))
    )
    (net (code "127") (name "unconnected-(D4-PadG15)") (class "Default")
      (node (ref "D4") (pin "G15") (pinfunction "G15_G15") (pintype "passive"))
    )
    (net (code "128") (name "unconnected-(D4-PadG16)") (class "Default")
      (node (ref "D4") (pin "G16") (pinfunction "G16_G16") (pintype "passive"))
    )
    (net (code "129") (name "unconnected-(D4-PadH15)") (class "Default")
      (node (ref "D4") (pin "H15") (pinfunction "H15_H15") (pintype "passive"))
    )
    (net (code "130") (name "unconnected-(D4-PadH16)") (class "Default")
      (node (ref "D4") (pin "H16") (pinfunction "H16_H16") (pintype "passive"))
    )
    (net (code "131") (name "unconnected-(D4-PadJ1)") (class "Default")
      (node (ref "D4") (pin "J1") (pinfunction "J1_J1") (pintype "passive"))
    )
    (net (code "132") (name "unconnected-(D4-PadJ2)") (class "Default")
      (node (ref "D4") (pin "J2") (pinfunction "J2_J2") (pintype "passive"))
    )
    (net (code "133") (name "unconnected-(D4-PadJ13)") (class "Default")
      (node (ref "D4") (pin "J13") (pinfunction "J13_J13") (pintype "passive"))
    )
    (net (code "134") (name "unconnected-(D4-PadJ14)") (class "Default")
      (node (ref "D4") (pin "J14") (pinfunction "J14_J14") (pintype "passive"))
    )
    (net (code "135") (name "unconnected-(D4-PadJ15)") (class "Default")
      (node (ref "D4") (pin "J15") (pinfunction "J15_J15") (pintype "passive"))
    )
    (net (code "136") (name "unconnected-(D4-PadJ16)") (class "Default")
      (node (ref "D4") (pin "J16") (pinfunction "J16_J16") (pintype "passive"))
    )
    (net (code "137") (name "unconnected-(D4-PadK1)") (class "Default")
      (node (ref "D4") (pin "K1") (pinfunction "K1_K1") (pintype "passive"))
    )
    (net (code "138") (name "unconnected-(D4-PadK2)") (class "Default")
      (node (ref "D4") (pin "K2") (pinfunction "K2_K2") (pintype "passive"))
    )
    (net (code "139") (name "unconnected-(D4-PadK5)") (class "Default")
      (node (ref "D4") (pin "K5") (pinfunction "K5_K5") (pintype "passive"))
    )
    (net (code "140") (name "unconnected-(D4-PadK15)") (class "Default")
      (node (ref "D4") (pin "K15") (pinfunction "K15_K15") (pintype "passive"))
    )
    (net (code "141") (name "unconnected-(D4-PadK16)") (class "Default")
      (node (ref "D4") (pin "K16") (pinfunction "K16_K16") (pintype "passive"))
    )
    (net (code "142") (name "unconnected-(D4-PadL1)") (class "Default")
      (node (ref "D4") (pin "L1") (pinfunction "L1_L1") (pintype "passive"))
    )
    (net (code "143") (name "unconnected-(D4-PadL2)") (class "Default")
      (node (ref "D4") (pin "L2") (pinfunction "L2_L2") (pintype "passive"))
    )
    (net (code "144") (name "unconnected-(D4-PadL3)") (class "Default")
      (node (ref "D4") (pin "L3") (pinfunction "L3_L3") (pintype "passive"))
    )
    (net (code "145") (name "unconnected-(D4-PadL4)") (class "Default")
      (node (ref "D4") (pin "L4") (pinfunction "L4_L4") (pintype "passive"))
    )
    (net (code "146") (name "unconnected-(D4-PadL7)") (class "Default")
      (node (ref "D4") (pin "L7") (pinfunction "L7_L7") (pintype "passive"))
    )
    (net (code "147") (name "unconnected-(D4-PadL8)") (class "Default")
      (node (ref "D4") (pin "L8") (pinfunction "L8_L8") (pintype "passive"))
    )
    (net (code "148") (name "unconnected-(D4-PadL13)") (class "Default")
      (node (ref "D4") (pin "L13") (pinfunction "L13_L13") (pintype "passive"))
    )
    (net (code "149") (name "unconnected-(D4-PadL14)") (class "Default")
      (node (ref "D4") (pin "L14") (pinfunction "L14_L14") (pintype "passive"))
    )
    (net (code "150") (name "unconnected-(D4-PadL15)") (class "Default")
      (node (ref "D4") (pin "L15") (pinfunction "L15_L15") (pintype "passive"))
    )
    (net (code "151") (name "unconnected-(D4-PadL16)") (class "Default")
      (node (ref "D4") (pin "L16") (pinfunction "L16_L16") (pintype "passive"))
    )
    (net (code "152") (name "unconnected-(D4-PadM1)") (class "Default")
      (node (ref "D4") (pin "M1") (pinfunction "M1_M1") (pintype "passive"))
    )
    (net (code "153") (name "unconnected-(D4-PadM2)") (class "Default")
      (node (ref "D4") (pin "M2") (pinfunction "M2_M2") (pintype "passive"))
    )
    (net (code "154") (name "unconnected-(D4-PadM6)") (class "Default")
      (node (ref "D4") (pin "M6") (pinfunction "M6_M6") (pintype "passive"))
    )
    (net (code "155") (name "unconnected-(D4-PadM7)") (class "Default")
      (node (ref "D4") (pin "M7") (pinfunction "M7_M7") (pintype "passive"))
    )
    (net (code "156") (name "unconnected-(D4-PadM8)") (class "Default")
      (node (ref "D4") (pin "M8") (pinfunction "M8_M8") (pintype "passive"))
    )
    (net (code "157") (name "unconnected-(D4-PadM10)") (class "Default")
      (node (ref "D4") (pin "M10") (pinfunction "M10_M10") (pintype "passive"))
    )
    (net (code "158") (name "unconnected-(D4-PadN1)") (class "Default")
      (node (ref "D4") (pin "N1") (pinfunction "N1_N1") (pintype "passive"))
    )
    (net (code "159") (name "unconnected-(D4-PadN2)") (class "Default")
      (node (ref "D4") (pin "N2") (pinfunction "N2_N2") (pintype "passive"))
    )
    (net (code "160") (name "unconnected-(D4-PadN3)") (class "Default")
      (node (ref "D4") (pin "N3") (pinfunction "N3_N3") (pintype "passive"))
    )
    (net (code "161") (name "unconnected-(D4-PadN5)") (class "Default")
      (node (ref "D4") (pin "N5") (pinfunction "N5_N5") (pintype "passive"))
    )
    (net (code "162") (name "unconnected-(D4-PadN6)") (class "Default")
      (node (ref "D4") (pin "N6") (pinfunction "N6_N6") (pintype "passive"))
    )
    (net (code "163") (name "unconnected-(D4-PadN8)") (class "Default")
      (node (ref "D4") (pin "N8") (pinfunction "N8_N8") (pintype "passive"))
    )
    (net (code "164") (name "unconnected-(D4-PadN9)") (class "Default")
      (node (ref "D4") (pin "N9") (pinfunction "N9_N9") (pintype "passive"))
    )
    (net (code "165") (name "unconnected-(D4-PadN11)") (class "Default")
      (node (ref "D4") (pin "N11") (pinfunction "N11_N11") (pintype "passive"))
    )
    (net (code "166") (name "unconnected-(D4-PadN12)") (class "Default")
      (node (ref "D4") (pin "N12") (pinfunction "N12_N12") (pintype "passive"))
    )
    (net (code "167") (name "unconnected-(D4-PadN14)") (class "Default")
      (node (ref "D4") (pin "N14") (pinfunction "N14_N14") (pintype "passive"))
    )
    (net (code "168") (name "unconnected-(D4-PadN15)") (class "Default")
      (node (ref "D4") (pin "N15") (pinfunction "N15_N15") (pintype "passive"))
    )
    (net (code "169") (name "unconnected-(D4-PadN16)") (class "Default")
      (node (ref "D4") (pin "N16") (pinfunction "N16_N16") (pintype "passive"))
    )
    (net (code "170") (name "unconnected-(D4-PadP1)") (class "Default")
      (node (ref "D4") (pin "P1") (pinfunction "P1_P1") (pintype "passive"))
    )
    (net (code "171") (name "unconnected-(D4-PadP2)") (class "Default")
      (node (ref "D4") (pin "P2") (pinfunction "P2_P2") (pintype "passive"))
    )
    (net (code "172") (name "unconnected-(D4-PadP3)") (class "Default")
      (node (ref "D4") (pin "P3") (pinfunction "P3_P3") (pintype "passive"))
    )
    (net (code "173") (name "unconnected-(D4-PadP6)") (class "Default")
      (node (ref "D4") (pin "P6") (pinfunction "P6_P6") (pintype "passive"))
    )
    (net (code "174") (name "unconnected-(D4-PadP7)") (class "Default")
      (node (ref "D4") (pin "P7") (pinfunction "P7_P7") (pintype "passive"))
    )
    (net (code "175") (name "unconnected-(D4-PadP9)") (class "Default")
      (node (ref "D4") (pin "P9") (pinfunction "P9_P9") (pintype "passive"))
    )
    (net (code "176") (name "unconnected-(D4-PadP11)") (class "Default")
      (node (ref "D4") (pin "P11") (pinfunction "P11_P11") (pintype "passive"))
    )
    (net (code "177") (name "unconnected-(D4-PadP14)") (class "Default")
      (node (ref "D4") (pin "P14") (pinfunction "P14_P14") (pintype "passive"))
    )
    (net (code "178") (name "unconnected-(D4-PadP15)") (class "Default")
      (node (ref "D4") (pin "P15") (pinfunction "P15_P15") (pintype "passive"))
    )
    (net (code "179") (name "unconnected-(D4-PadP16)") (class "Default")
      (node (ref "D4") (pin "P16") (pinfunction "P16_P16") (pintype "passive"))
    )
    (net (code "180") (name "unconnected-(D4-PadR1)") (class "Default")
      (node (ref "D4") (pin "R1") (pinfunction "R1_R1") (pintype "passive"))
    )
    (net (code "181") (name "unconnected-(D4-PadR3)") (class "Default")
      (node (ref "D4") (pin "R3") (pinfunction "R3_R3") (pintype "passive"))
    )
    (net (code "182") (name "unconnected-(D4-PadR4)") (class "Default")
      (node (ref "D4") (pin "R4") (pinfunction "R4_R4") (pintype "passive"))
    )
    (net (code "183") (name "unconnected-(D4-PadR5)") (class "Default")
      (node (ref "D4") (pin "R5") (pinfunction "R5_R5") (pintype "passive"))
    )
    (net (code "184") (name "unconnected-(D4-PadR6)") (class "Default")
      (node (ref "D4") (pin "R6") (pinfunction "R6_R6") (pintype "passive"))
    )
    (net (code "185") (name "unconnected-(D4-PadR7)") (class "Default")
      (node (ref "D4") (pin "R7") (pinfunction "R7_R7") (pintype "passive"))
    )
    (net (code "186") (name "unconnected-(D4-PadR8)") (class "Default")
      (node (ref "D4") (pin "R8") (pinfunction "R8_R8") (pintype "passive"))
    )
    (net (code "187") (name "unconnected-(D4-PadR9)") (class "Default")
      (node (ref "D4") (pin "R9") (pinfunction "R9_R9") (pintype "passive"))
    )
    (net (code "188") (name "unconnected-(D4-PadR10)") (class "Default")
      (node (ref "D4") (pin "R10") (pinfunction "R10_R10") (pintype "passive"))
    )
    (net (code "189") (name "unconnected-(D4-PadR11)") (class "Default")
      (node (ref "D4") (pin "R11") (pinfunction "R11_R11") (pintype "passive"))
    )
    (net (code "190") (name "unconnected-(D4-PadR12)") (class "Default")
      (node (ref "D4") (pin "R12") (pinfunction "R12_R12") (pintype "passive"))
    )
    (net (code "191") (name "unconnected-(D4-PadR13)") (class "Default")
      (node (ref "D4") (pin "R13") (pinfunction "R13_R13") (pintype "passive"))
    )
    (net (code "192") (name "unconnected-(D4-PadR14)") (class "Default")
      (node (ref "D4") (pin "R14") (pinfunction "R14_R14") (pintype "passive"))
    )
    (net (code "193") (name "unconnected-(D4-PadR16)") (class "Default")
      (node (ref "D4") (pin "R16") (pinfunction "R16_R16") (pintype "passive"))
    )
    (net (code "194") (name "unconnected-(D4-PadT2)") (class "Default")
      (node (ref "D4") (pin "T2") (pinfunction "T2_T2") (pintype "passive"))
    )
    (net (code "195") (name "unconnected-(D4-PadT3)") (class "Default")
      (node (ref "D4") (pin "T3") (pinfunction "T3_T3") (pintype "passive"))
    )
    (net (code "196") (name "unconnected-(D4-PadT4)") (class "Default")
      (node (ref "D4") (pin "T4") (pinfunction "T4_T4") (pintype "passive"))
    )
    (net (code "197") (name "unconnected-(D4-PadT5)") (class "Default")
      (node (ref "D4") (pin "T5") (pinfunction "T5_T5") (pintype "passive"))
    )
    (net (code "198") (name "unconnected-(D4-PadT6)") (class "Default")
      (node (ref "D4") (pin "T6") (pinfunction "T6_T6") (pintype "passive"))
    )
    (net (code "199") (name "unconnected-(D4-PadT7)") (class "Default")
      (node (ref "D4") (pin "T7") (pinfunction "T7_T7") (pintype "passive"))
    )
    (net (code "200") (name "unconnected-(D4-PadT8)") (class "Default")
      (node (ref "D4") (pin "T8") (pinfunction "T8_T8") (pintype "passive"))
    )
    (net (code "201") (name "unconnected-(D4-PadT9)") (class "Default")
      (node (ref "D4") (pin "T9") (pinfunction "T9_T9") (pintype "passive"))
    )
    (net (code "202") (name "unconnected-(D4-PadT10)") (class "Default")
      (node (ref "D4") (pin "T10") (pinfunction "T10_T10") (pintype "passive"))
    )
    (net (code "203") (name "unconnected-(D4-PadT11)") (class "Default")
      (node (ref "D4") (pin "T11") (pinfunction "T11_T11") (pintype "passive"))
    )
    (net (code "204") (name "unconnected-(D4-PadT14)") (class "Default")
      (node (ref "D4") (pin "T14") (pinfunction "T14_T14") (pintype "passive"))
    )
    (net (code "205") (name "unconnected-(D4-PadT15)") (class "Default")
      (node (ref "D4") (pin "T15") (pinfunction "T15_T15") (pintype "passive"))
    )
    (net (code "206") (name "unconnected-(X2-Pad6)") (class "Default")
      (node (ref "X2") (pin "6") (pinfunction "6_6") (pintype "passive"))
    )
    (net (code "207") (name "unconnected-(X2-Pad7)") (class "Default")
      (node (ref "X2") (pin "7") (pinfunction "7_7") (pintype "passive"))
    )
    (net (code "208") (name "unconnected-(X2-Pad8)") (class "Default")
      (node (ref "X2") (pin "8") (pinfunction "8_8") (pintype "passive"))
    )
    (net (code "209") (name "unconnected-(XC1-Pad33)") (class "Default")
      (node (ref "XC1") (pin "33") (pinfunction "33_33") (pintype "passive"))
    )
    (net (code "210") (name "unconnected-(XC1-Pad34)") (class "Default")
      (node (ref "XC1") (pin "34") (pinfunction "34_34") (pintype "passive"))
    )
  )
)
